# 526_outin_pico_pdm.net
KiCad netlist of a schematic drawn in EAGLE
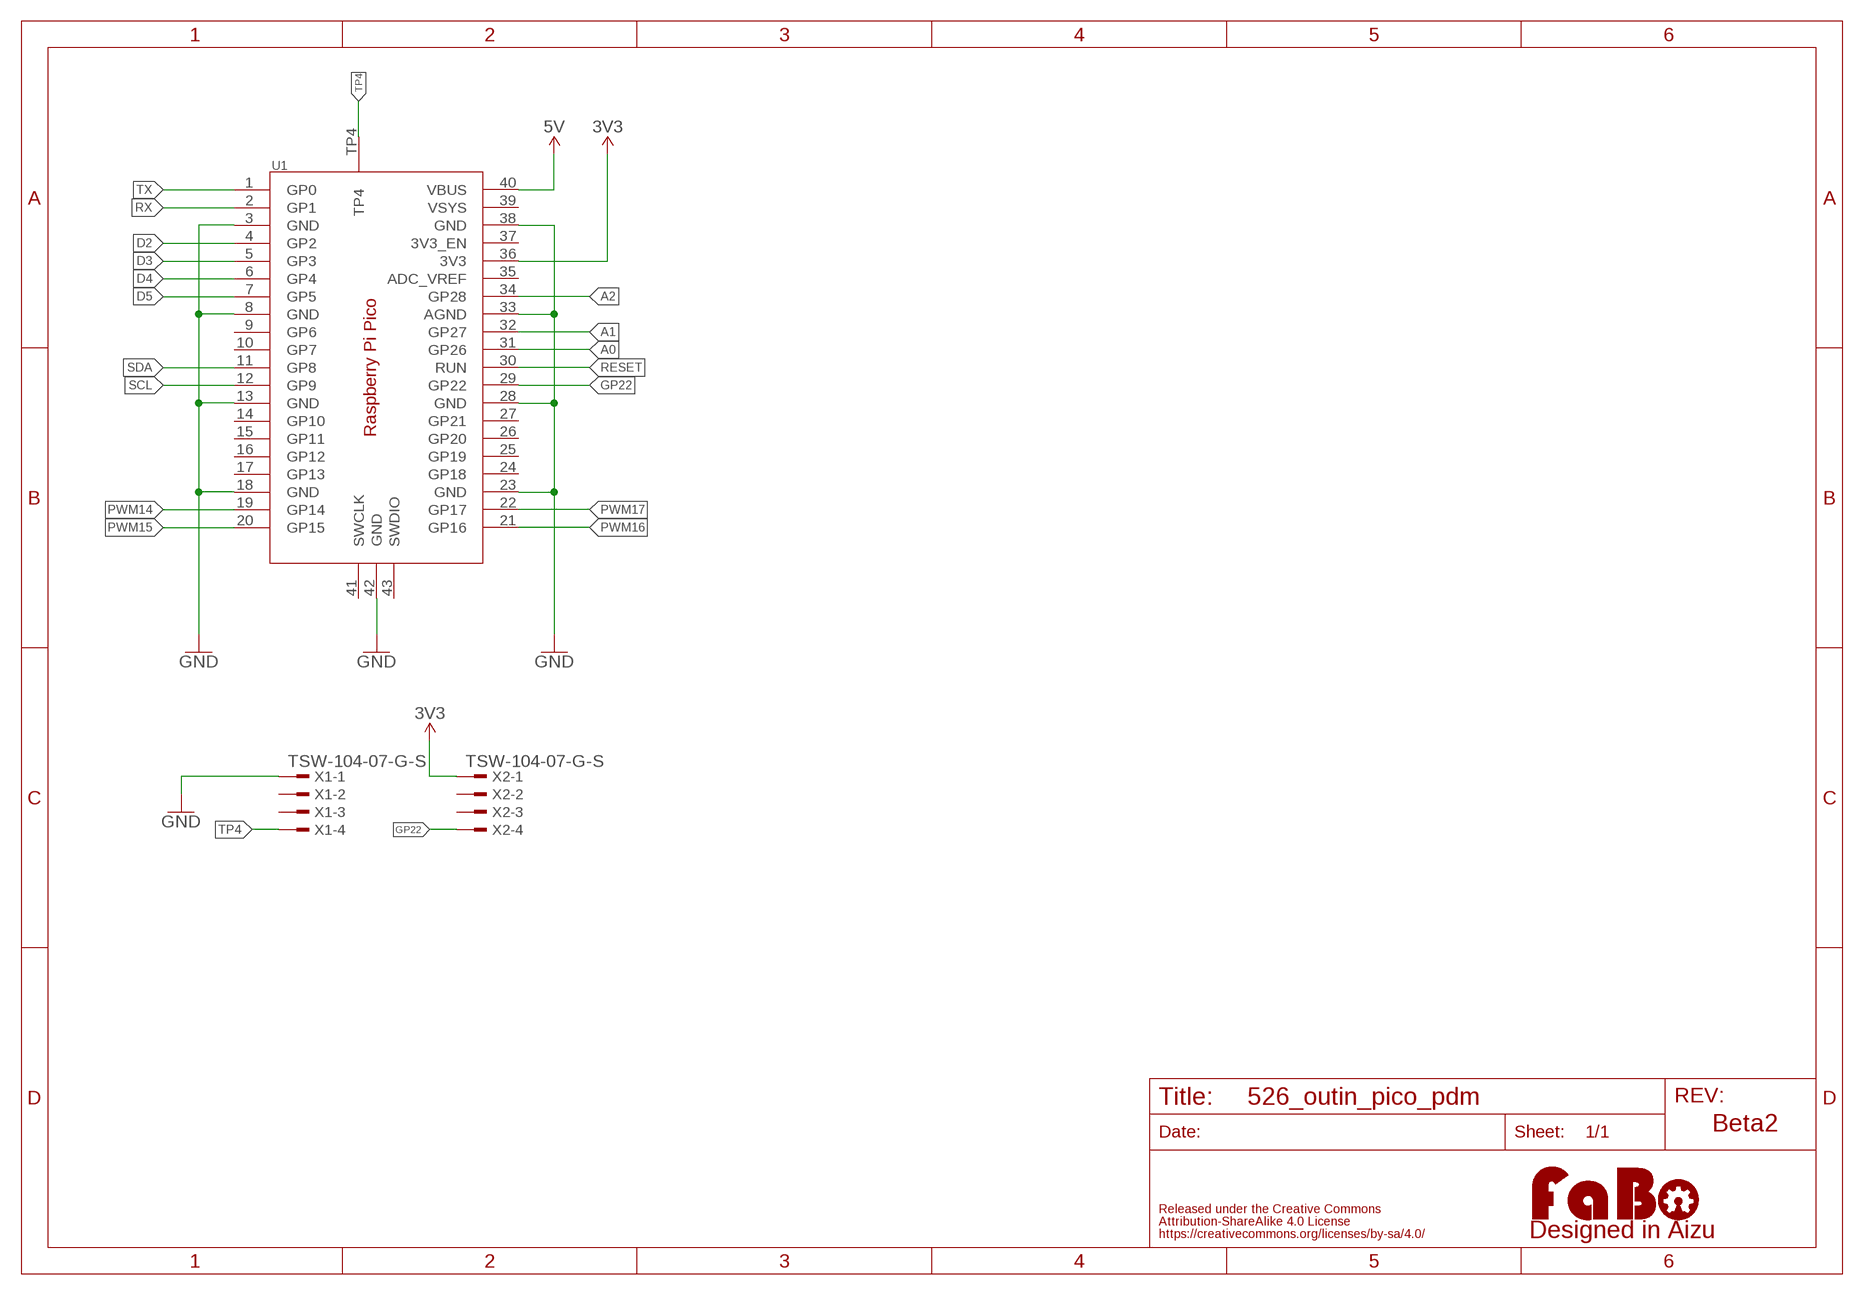
[diagram p0: schematic, sheet 1]

(export (version "E")
  (design (tool "Eeschema 10.0.6"))
  (components
    (comp (ref "LOGO2")
      (value "LOGO_FABO-M")
      (footprint "eagle-import:LOGO_FABO_M")
      (libsource (lib "eagle-import") (part "LOGO_FABO-M"))
    )
    (comp (ref "U1")
      (value "RASPBERRY_PI_PICOPDM")
      (footprint "eagle-import:RASPBERRY_PI_PICO_HEADER")
      (libsource (lib "eagle-import") (part "RASPBERRY_PI_PICOPDM"))
    )
    (comp (ref "X1")
      (value "TSW-104-07-G-S")
      (footprint "eagle-import:TSW-104-XX-G-S")
      (fields (field (name "MF") "Samtec Inc."))
      (libsource (lib "eagle-import") (part "TSW-104--G-S07"))
    )
    (comp (ref "X2")
      (value "TSW-104-07-G-S")
      (footprint "eagle-import:TSW-104-XX-G-S")
      (fields (field (name "MF") "Samtec Inc."))
      (libsource (lib "eagle-import") (part "TSW-104--G-S07"))
    )
  )
  (nets
    (net (code "1") (name "3V3") (class "Default")
      (node (ref "U1") (pin "36") (pinfunction "3V3_36") (pintype "bidirectional"))
      (node (ref "X2") (pin "1") (pinfunction "1_1") (pintype "passive"))
    )
    (net (code "2") (name "5V") (class "Default")
      (node (ref "U1") (pin "40") (pinfunction "VBUS_40") (pintype "bidirectional"))
    )
    (net (code "3") (name "A0") (class "Default")
      (node (ref "U1") (pin "31") (pinfunction "GP26_31") (pintype "bidirectional"))
    )
    (net (code "4") (name "A1") (class "Default")
      (node (ref "U1") (pin "32") (pinfunction "GP27_32") (pintype "bidirectional"))
    )
    (net (code "5") (name "A2") (class "Default")
      (node (ref "U1") (pin "34") (pinfunction "GP28_34") (pintype "bidirectional"))
    )
    (net (code "6") (name "D2") (class "Default")
      (node (ref "U1") (pin "4") (pinfunction "GP2_4") (pintype "bidirectional"))
    )
    (net (code "7") (name "D3") (class "Default")
      (node (ref "U1") (pin "5") (pinfunction "GP3_5") (pintype "bidirectional"))
    )
    (net (code "8") (name "D4") (class "Default")
      (node (ref "U1") (pin "6") (pinfunction "GP4_6") (pintype "bidirectional"))
    )
    (net (code "9") (name "D5") (class "Default")
      (node (ref "U1") (pin "7") (pinfunction "GP5_7") (pintype "bidirectional"))
    )
    (net (code "10") (name "GND") (class "Default")
      (node (ref "U1") (pin "13") (pinfunction "GND_13") (pintype "bidirectional"))
      (node (ref "U1") (pin "18") (pinfunction "GND_18") (pintype "bidirectional"))
      (node (ref "U1") (pin "23") (pinfunction "GND_23") (pintype "bidirectional"))
      (node (ref "U1") (pin "28") (pinfunction "GND_28") (pintype "bidirectional"))
      (node (ref "U1") (pin "3") (pinfunction "GND_3") (pintype "bidirectional"))
      (node (ref "U1") (pin "33") (pinfunction "AGND_33") (pintype "bidirectional"))
      (node (ref "U1") (pin "38") (pinfunction "GND_38") (pintype "bidirectional"))
      (node (ref "U1") (pin "42") (pinfunction "GND_42") (pintype "bidirectional"))
      (node (ref "U1") (pin "8") (pinfunction "GND_8") (pintype "bidirectional"))
      (node (ref "X1") (pin "1") (pinfunction "1_1") (pintype "passive"))
    )
    (net (code "11") (name "GP22") (class "Default")
      (node (ref "U1") (pin "29") (pinfunction "GP22_29") (pintype "bidirectional"))
      (node (ref "X2") (pin "4") (pinfunction "1_4") (pintype "passive"))
    )
    (net (code "12") (name "PWM14") (class "Default")
      (node (ref "U1") (pin "19") (pinfunction "GP14_19") (pintype "bidirectional"))
    )
    (net (code "13") (name "PWM15") (class "Default")
      (node (ref "U1") (pin "20") (pinfunction "GP15_20") (pintype "bidirectional"))
    )
    (net (code "14") (name "PWM16") (class "Default")
      (node (ref "U1") (pin "21") (pinfunction "GP16_21") (pintype "bidirectional"))
    )
    (net (code "15") (name "PWM17") (class "Default")
      (node (ref "U1") (pin "22") (pinfunction "GP17_22") (pintype "bidirectional"))
    )
    (net (code "16") (name "RESET") (class "Default")
      (node (ref "U1") (pin "30") (pinfunction "RUN_30") (pintype "bidirectional"))
    )
    (net (code "17") (name "RX") (class "Default")
      (node (ref "U1") (pin "2") (pinfunction "GP1_2") (pintype "bidirectional"))
    )
    (net (code "18") (name "SCL") (class "Default")
      (node (ref "U1") (pin "12") (pinfunction "GP9_12") (pintype "bidirectional"))
    )
    (net (code "19") (name "SDA") (class "Default")
      (node (ref "U1") (pin "11") (pinfunction "GP8_11") (pintype "bidirectional"))
    )
    (net (code "20") (name "TP4") (class "Default")
      (node (ref "U1") (pin "TP4") (pinfunction "TP4_TP4") (pintype "bidirectional"))
      (node (ref "X1") (pin "4") (pinfunction "1_4") (pintype "passive"))
    )
    (net (code "21") (name "TX") (class "Default")
      (node (ref "U1") (pin "1") (pinfunction "GP0_1") (pintype "bidirectional"))
    )
    (net (code "22") (name "unconnected-(U1-3V3_EN-Pad37)") (class "Default")
      (node (ref "U1") (pin "37") (pinfunction "3V3_EN_37") (pintype "bidirectional"))
    )
    (net (code "23") (name "unconnected-(U1-ADC_VREF-Pad35)") (class "Default")
      (node (ref "U1") (pin "35") (pinfunction "ADC_VREF_35") (pintype "bidirectional"))
    )
    (net (code "24") (name "unconnected-(U1-GP6-Pad9)") (class "Default")
      (node (ref "U1") (pin "9") (pinfunction "GP6_9") (pintype "bidirectional"))
    )
    (net (code "25") (name "unconnected-(U1-GP7-Pad10)") (class "Default")
      (node (ref "U1") (pin "10") (pinfunction "GP7_10") (pintype "bidirectional"))
    )
    (net (code "26") (name "unconnected-(U1-GP10-Pad14)") (class "Default")
      (node (ref "U1") (pin "14") (pinfunction "GP10_14") (pintype "bidirectional"))
    )
    (net (code "27") (name "unconnected-(U1-GP11-Pad15)") (class "Default")
      (node (ref "U1") (pin "15") (pinfunction "GP11_15") (pintype "bidirectional"))
    )
    (net (code "28") (name "unconnected-(U1-GP12-Pad16)") (class "Default")
      (node (ref "U1") (pin "16") (pinfunction "GP12_16") (pintype "bidirectional"))
    )
    (net (code "29") (name "unconnected-(U1-GP13-Pad17)") (class "Default")
      (node (ref "U1") (pin "17") (pinfunction "GP13_17") (pintype "bidirectional"))
    )
    (net (code "30") (name "unconnected-(U1-GP18-Pad24)") (class "Default")
      (node (ref "U1") (pin "24") (pinfunction "GP18_24") (pintype "bidirectional"))
    )
    (net (code "31") (name "unconnected-(U1-GP19-Pad25)") (class "Default")
      (node (ref "U1") (pin "25") (pinfunction "GP19_25") (pintype "bidirectional"))
    )
    (net (code "32") (name "unconnected-(U1-GP20-Pad26)") (class "Default")
      (node (ref "U1") (pin "26") (pinfunction "GP20_26") (pintype "bidirectional"))
    )
    (net (code "33") (name "unconnected-(U1-GP21-Pad27)") (class "Default")
      (node (ref "U1") (pin "27") (pinfunction "GP21_27") (pintype "bidirectional"))
    )
    (net (code "34") (name "unconnected-(U1-SWCLK-Pad41)") (class "Default")
      (node (ref "U1") (pin "41") (pinfunction "SWCLK_41") (pintype "bidirectional"))
    )
    (net (code "35") (name "unconnected-(U1-SWDIO-Pad43)") (class "Default")
      (node (ref "U1") (pin "43") (pinfunction "SWDIO_43") (pintype "bidirectional"))
    )
    (net (code "36") (name "unconnected-(U1-VSYS-Pad39)") (class "Default")
      (node (ref "U1") (pin "39") (pinfunction "VSYS_39") (pintype "bidirectional"))
    )
    (net (code "37") (name "unconnected-(X1B-1-Pad2)") (class "Default")
      (node (ref "X1") (pin "2") (pinfunction "1_2") (pintype "passive"))
    )
    (net (code "38") (name "unconnected-(X1C-1-Pad3)") (class "Default")
      (node (ref "X1") (pin "3") (pinfunction "1_3") (pintype "passive"))
    )
    (net (code "39") (name "unconnected-(X2B-1-Pad2)") (class "Default")
      (node (ref "X2") (pin "2") (pinfunction "1_2") (pintype "passive"))
    )
    (net (code "40") (name "unconnected-(X2C-1-Pad3)") (class "Default")
      (node (ref "X2") (pin "3") (pinfunction "1_3") (pintype "passive"))
    )
  )
)
